# VOUT_2-5V.net
KiCad netlist of a schematic drawn in Altium Designer
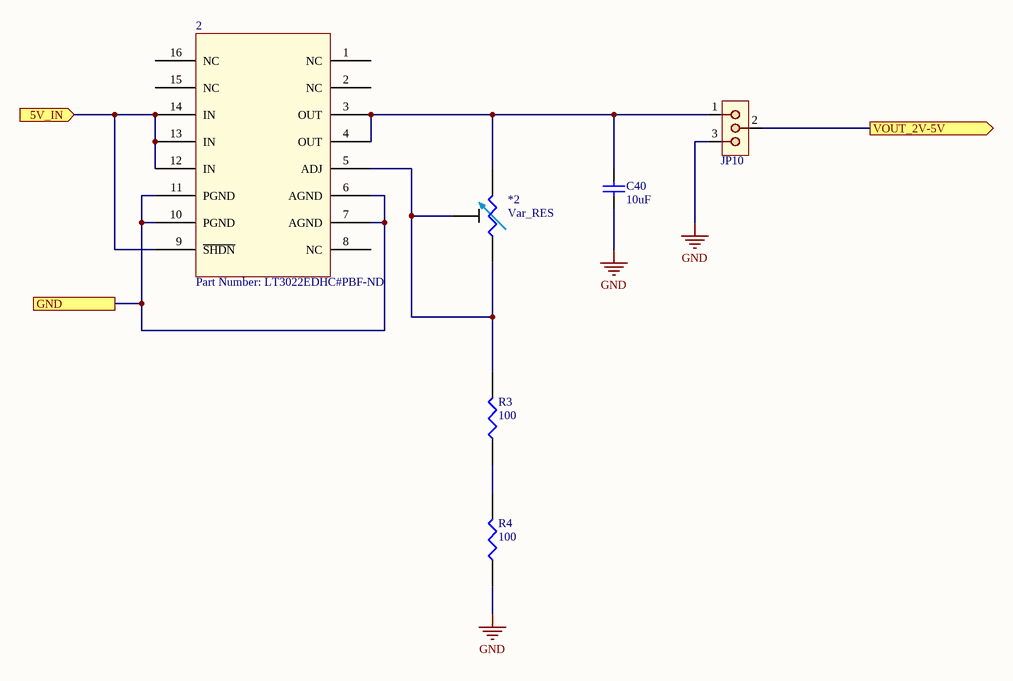
[diagram p0: VOUT_2-5V.SchDoc]

(export (version "E")
  (design (tool "Eeschema 10.0.6"))
  (components
    (comp (ref "*2")
      (value "Var_RES")
      (footprint "res_var_5turn")
      (libsource (lib "CLS_Library") (part "Var_RES"))
    )
    (comp (ref "2")
      (value "Part Number: LT3022EDHC#PBF-ND")
      (footprint "LT3022")
      (description "Linear Voltage Regulator IC Positive Adjustable 1 Output 1A 16-DFN (5x3)")
      (libsource (lib "CLS_Library") (part "LT3022"))
    )
    (comp (ref "C40")
      (value "10uF")
      (footprint "CLS_Library:C0805")
      (description "Cap 10uF")
      (fields
        (field (name "MANUFACTURER") "Taiyo Yuden")
        (field (name "MANUFACTURER PART NUMBER") "UMK212SD103KD-T")
      )
      (libsource (lib "Chip1_TestBoard") (part "Cap 10uF"))
    )
    (comp (ref "JP10")
      (value "Jumper")
      (footprint "01x03_0.1in_th_straight_b_nom")
      (description "01X03 generic terminal connector")
      (libsource (lib "CLS_Library") (part "Jumper-01x03"))
    )
    (comp (ref "R3") (value "100") (footprint "R0805") (libsource (lib "Chip1_TestBoard") (part "Res 100")))
    (comp (ref "R4") (value "100") (footprint "R0805") (libsource (lib "Chip1_TestBoard") (part "Res 100")))
  )
  (nets
    (net (code "1") (name "/5V_IN") (class "Default")
      (node (ref "2") (pin "12") (pinfunction "IN_12") (pintype "passive"))
      (node (ref "2") (pin "13") (pinfunction "IN_13") (pintype "passive"))
      (node (ref "2") (pin "14") (pinfunction "IN_14") (pintype "passive"))
      (node (ref "2") (pin "9") (pinfunction "~{SHDN}_9") (pintype "passive"))
    )
    (net (code "2") (name "/VOUT_2V-5V") (class "Default")
      (node (ref "JP10") (pin "2") (pinfunction "2_2") (pintype "passive"))
    )
    (net (code "3") (name "GND") (class "Default")
      (node (ref "2") (pin "10") (pinfunction "PGND_10") (pintype "passive"))
      (node (ref "2") (pin "11") (pinfunction "PGND_11") (pintype "passive"))
      (node (ref "2") (pin "6") (pinfunction "AGND_6") (pintype "passive"))
      (node (ref "2") (pin "7") (pinfunction "AGND_7") (pintype "passive"))
      (node (ref "C40") (pin "1") (pinfunction "1_1") (pintype "passive"))
      (node (ref "JP10") (pin "3") (pinfunction "3_3") (pintype "passive"))
      (node (ref "R4") (pin "1") (pinfunction "1_1") (pintype "passive"))
    )
    (net (code "4") (name "Net-(*2-Pad3)") (class "Default")
      (node (ref "*2") (pin "3") (pinfunction "3_3") (pintype "passive"))
      (node (ref "2") (pin "3") (pinfunction "OUT_3") (pintype "passive"))
      (node (ref "2") (pin "4") (pinfunction "OUT_4") (pintype "passive"))
      (node (ref "C40") (pin "2") (pinfunction "2_2") (pintype "passive"))
      (node (ref "JP10") (pin "1") (pinfunction "1_1") (pintype "passive"))
    )
    (net (code "5") (name "Net-(2-ADJ)") (class "Default")
      (node (ref "*2") (pin "1") (pinfunction "1_1") (pintype "passive"))
      (node (ref "*2") (pin "2") (pinfunction "2_2") (pintype "passive"))
      (node (ref "2") (pin "5") (pinfunction "ADJ_5") (pintype "passive"))
      (node (ref "R3") (pin "2") (pinfunction "2_2") (pintype "passive"))
    )
    (net (code "6") (name "Net-(R3-Pad1)") (class "Default")
      (node (ref "R3") (pin "1") (pinfunction "1_1") (pintype "passive"))
      (node (ref "R4") (pin "2") (pinfunction "2_2") (pintype "passive"))
    )
    (net (code "7") (name "unconnected-(2-NC-Pad1)") (class "Default")
      (node (ref "2") (pin "1") (pinfunction "NC_1") (pintype "passive"))
    )
    (net (code "8") (name "unconnected-(2-NC-Pad2)") (class "Default")
      (node (ref "2") (pin "2") (pinfunction "NC_2") (pintype "passive"))
    )
    (net (code "9") (name "unconnected-(2-NC-Pad8)") (class "Default")
      (node (ref "2") (pin "8") (pinfunction "NC_8") (pintype "passive"))
    )
    (net (code "10") (name "unconnected-(2-NC-Pad15)") (class "Default")
      (node (ref "2") (pin "15") (pinfunction "NC_15") (pintype "passive"))
    )
    (net (code "11") (name "unconnected-(2-NC-Pad16)") (class "Default")
      (node (ref "2") (pin "16") (pinfunction "NC_16") (pintype "passive"))
    )
  )
)
